# P01_Power.net
KiCad netlist of a schematic drawn in Altium Designer
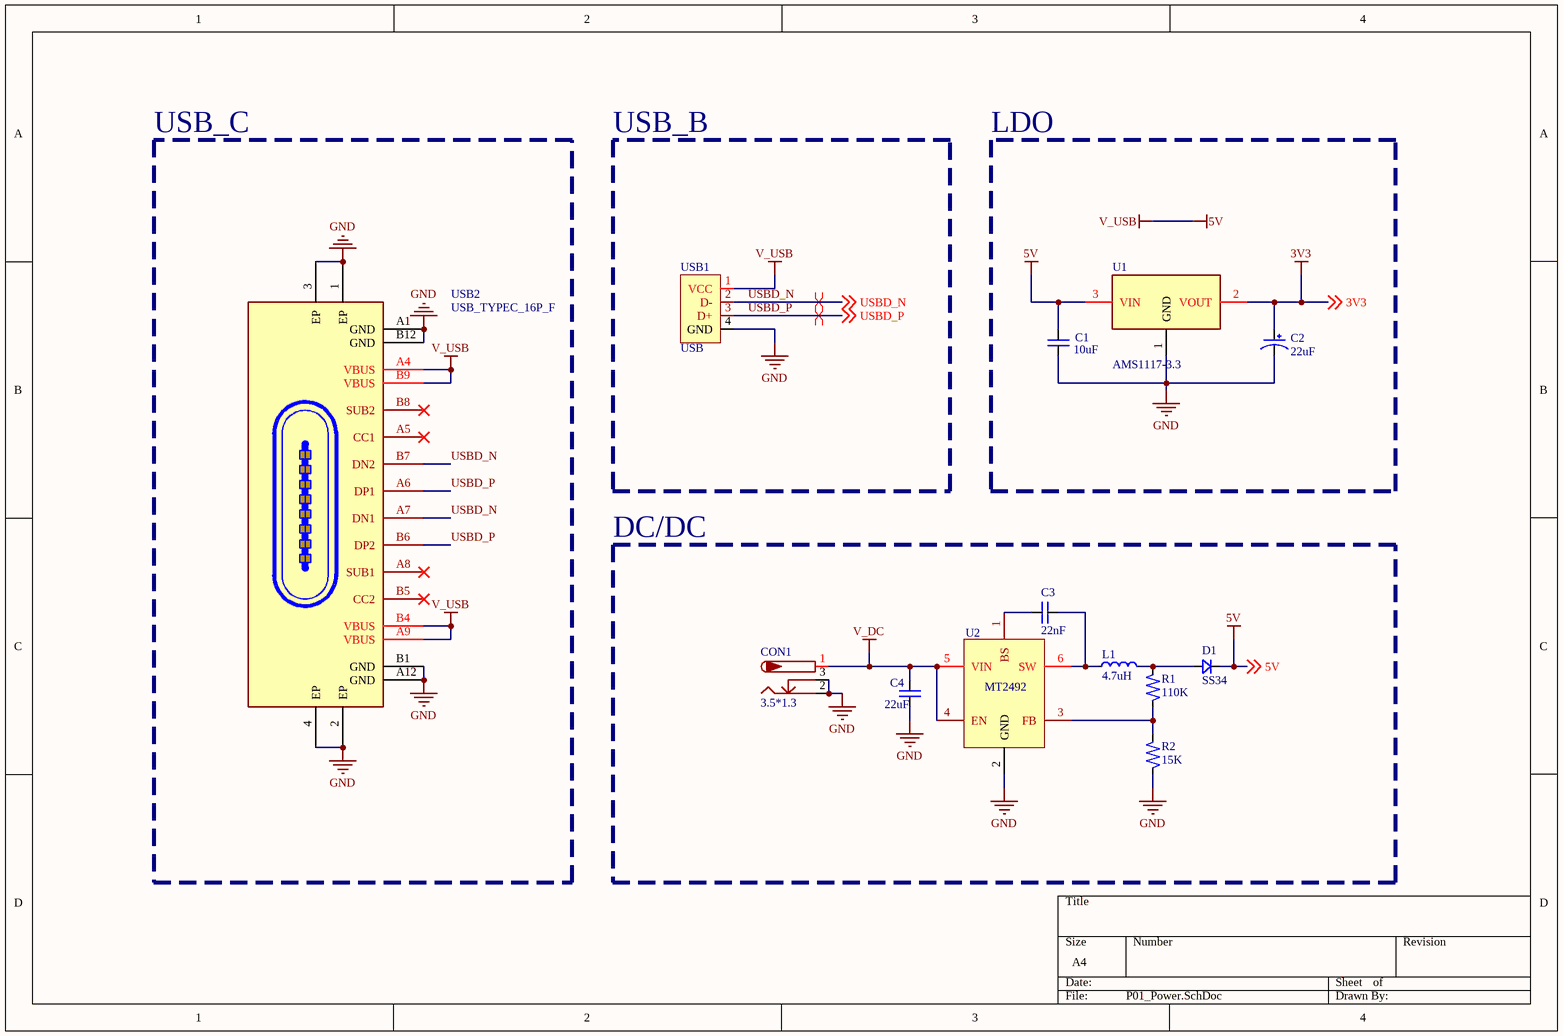
[diagram p0: P01_Power.SchDoc]

(export (version "E")
  (design (tool "Eeschema 10.0.6"))
  (components
    (comp (ref "C1")
      (value "10uF")
      (footprint "C_0805")
      (description "无极性电容")
      (libsource (lib "Schlib") (part "C"))
    )
    (comp (ref "C2")
      (value "22uF")
      (footprint "CASE-A-3216")
      (description "Tantalum Capacitor\r\n钽电容")
      (libsource (lib "Schlib") (part "C_Tan"))
    )
    (comp (ref "C3")
      (value "22nF")
      (footprint "C_0603")
      (description "无极性电容")
      (libsource (lib "Schlib") (part "C"))
    )
    (comp (ref "C4")
      (value "22uF")
      (footprint "C_0603")
      (description "无极性电容")
      (libsource (lib "Schlib") (part "C"))
    )
    (comp (ref "CON1")
      (value "3.5*1.3")
      (footprint "DC_Input")
      (description "低压电源接口")
      (libsource (lib "Schlib") (part "DC_Input"))
    )
    (comp (ref "D1")
      (value "SS34")
      (footprint "SMA")
      (description "Diode")
      (libsource (lib "Schlib") (part "D"))
    )
    (comp (ref "L1")
      (value "4.7uH")
      (footprint "L_SMD0420")
      (description "Inductor")
      (libsource (lib "Schlib") (part "L"))
    )
    (comp (ref "R1")
      (value "110K")
      (footprint "R_0603")
      (description "Resistor")
      (libsource (lib "Schlib") (part "R"))
    )
    (comp (ref "R2")
      (value "15K")
      (footprint "R_0603")
      (description "Resistor")
      (libsource (lib "Schlib") (part "R"))
    )
    (comp (ref "U1")
      (value "AMS1117-3.3")
      (footprint "SOT-223")
      (description "LDO to 3V3")
      (libsource (lib "Schlib") (part "AMS1117-3.3"))
    )
    (comp (ref "U2") (value "MT2492") (footprint "SOT23-6") (libsource (lib "Schlib") (part "MT2492")))
    (comp (ref "USB1") (value "USB") (footprint "USB_TYPEB_4P") (libsource (lib "Schlib") (part "USB_4Pin")))
    (comp (ref "USB2")
      (value "USB_TYPEC_16P_F")
      (footprint "USB_TYPEC_16P")
      (description "USB母座，TYPEC，16pin")
      (libsource (lib "Schlib") (part "USB_TYPEC_16P_F"))
    )
  )
  (nets
    (net (code "1") (name "3V3") (class "Default")
      (node (ref "C2") (pin "1") (pinfunction "1_1") (pintype "passive"))
      (node (ref "U1") (pin "2") (pinfunction "VOUT_2") (pintype "passive"))
    )
    (net (code "2") (name "5V") (class "Default")
      (node (ref "C1") (pin "1") (pinfunction "1_1") (pintype "passive"))
      (node (ref "D1") (pin "1") (pinfunction "1_1") (pintype "passive"))
      (node (ref "U1") (pin "3") (pinfunction "VIN_3") (pintype "passive"))
      (node (ref "USB1") (pin "1") (pinfunction "VCC_1") (pintype "passive"))
      (node (ref "USB2") (pin "A4") (pinfunction "VBUS_A4") (pintype "passive"))
      (node (ref "USB2") (pin "A9") (pinfunction "VBUS_A9") (pintype "passive"))
      (node (ref "USB2") (pin "B4") (pinfunction "VBUS_B4") (pintype "passive"))
      (node (ref "USB2") (pin "B9") (pinfunction "VBUS_B9") (pintype "passive"))
    )
    (net (code "3") (name "GND") (class "Default")
      (node (ref "C1") (pin "2") (pinfunction "2_2") (pintype "passive"))
      (node (ref "C2") (pin "2") (pinfunction "2_2") (pintype "passive"))
      (node (ref "C4") (pin "2") (pinfunction "2_2") (pintype "passive"))
      (node (ref "CON1") (pin "2") (pintype "power_in"))
      (node (ref "CON1") (pin "3") (pintype "power_in"))
      (node (ref "R2") (pin "1") (pinfunction "1_1") (pintype "passive"))
      (node (ref "U1") (pin "1") (pinfunction "GND_1") (pintype "passive"))
      (node (ref "U2") (pin "2") (pinfunction "GND_2") (pintype "passive"))
      (node (ref "USB1") (pin "4") (pinfunction "GND_4") (pintype "passive"))
      (node (ref "USB2") (pin "1") (pinfunction "EP_1") (pintype "passive"))
      (node (ref "USB2") (pin "2") (pinfunction "EP_2") (pintype "passive"))
      (node (ref "USB2") (pin "3") (pinfunction "EP_3") (pintype "passive"))
      (node (ref "USB2") (pin "4") (pinfunction "EP_4") (pintype "passive"))
      (node (ref "USB2") (pin "A1") (pinfunction "GND_A1") (pintype "passive"))
      (node (ref "USB2") (pin "A12") (pinfunction "GND_A12") (pintype "passive"))
      (node (ref "USB2") (pin "B1") (pinfunction "GND_B1") (pintype "passive"))
      (node (ref "USB2") (pin "B12") (pinfunction "GND_B12") (pintype "passive"))
    )
    (net (code "4") (name "Net-(D1-Pad2)") (class "Default")
      (node (ref "D1") (pin "2") (pinfunction "2_2") (pintype "passive"))
      (node (ref "L1") (pin "1") (pinfunction "1_1") (pintype "passive"))
      (node (ref "R1") (pin "2") (pinfunction "2_2") (pintype "passive"))
    )
    (net (code "5") (name "Net-(U2-BS)") (class "Default")
      (node (ref "C3") (pin "1") (pinfunction "1_1") (pintype "passive"))
      (node (ref "U2") (pin "1") (pinfunction "BS_1") (pintype "passive"))
    )
    (net (code "6") (name "Net-(U2-FB)") (class "Default")
      (node (ref "R1") (pin "1") (pinfunction "1_1") (pintype "passive"))
      (node (ref "R2") (pin "2") (pinfunction "2_2") (pintype "passive"))
      (node (ref "U2") (pin "3") (pinfunction "FB_3") (pintype "passive"))
    )
    (net (code "7") (name "Net-(U2-SW)") (class "Default")
      (node (ref "C3") (pin "2") (pinfunction "2_2") (pintype "passive"))
      (node (ref "L1") (pin "2") (pinfunction "2_2") (pintype "passive"))
      (node (ref "U2") (pin "6") (pinfunction "SW_6") (pintype "passive"))
    )
    (net (code "8") (name "USBD_N") (class "Default")
      (node (ref "USB1") (pin "2") (pinfunction "D-_2") (pintype "passive"))
      (node (ref "USB2") (pin "A7") (pinfunction "DN1_A7") (pintype "passive"))
      (node (ref "USB2") (pin "B7") (pinfunction "DN2_B7") (pintype "passive"))
    )
    (net (code "9") (name "USBD_P") (class "Default")
      (node (ref "USB1") (pin "3") (pinfunction "D+_3") (pintype "passive"))
      (node (ref "USB2") (pin "A6") (pinfunction "DP1_A6") (pintype "passive"))
      (node (ref "USB2") (pin "B6") (pinfunction "DP2_B6") (pintype "passive"))
    )
    (net (code "10") (name "V_DC") (class "Default")
      (node (ref "C4") (pin "1") (pinfunction "1_1") (pintype "passive"))
      (node (ref "CON1") (pin "1") (pintype "power_in"))
      (node (ref "U2") (pin "4") (pinfunction "EN_4") (pintype "passive"))
      (node (ref "U2") (pin "5") (pinfunction "VIN_5") (pintype "passive"))
    )
    (net (code "11") (name "unconnected-(USB2-CC1-PadA5)") (class "Default")
      (node (ref "USB2") (pin "A5") (pinfunction "CC1_A5") (pintype "passive+no_connect"))
    )
    (net (code "12") (name "unconnected-(USB2-CC2-PadB5)") (class "Default")
      (node (ref "USB2") (pin "B5") (pinfunction "CC2_B5") (pintype "passive+no_connect"))
    )
    (net (code "13") (name "unconnected-(USB2-SUB1-PadA8)") (class "Default")
      (node (ref "USB2") (pin "A8") (pinfunction "SUB1_A8") (pintype "passive+no_connect"))
    )
    (net (code "14") (name "unconnected-(USB2-SUB2-PadB8)") (class "Default")
      (node (ref "USB2") (pin "B8") (pinfunction "SUB2_B8") (pintype "passive+no_connect"))
    )
  )
)
